# MB_RELAY.net
KiCad netlist of a schematic drawn in Altium Designer
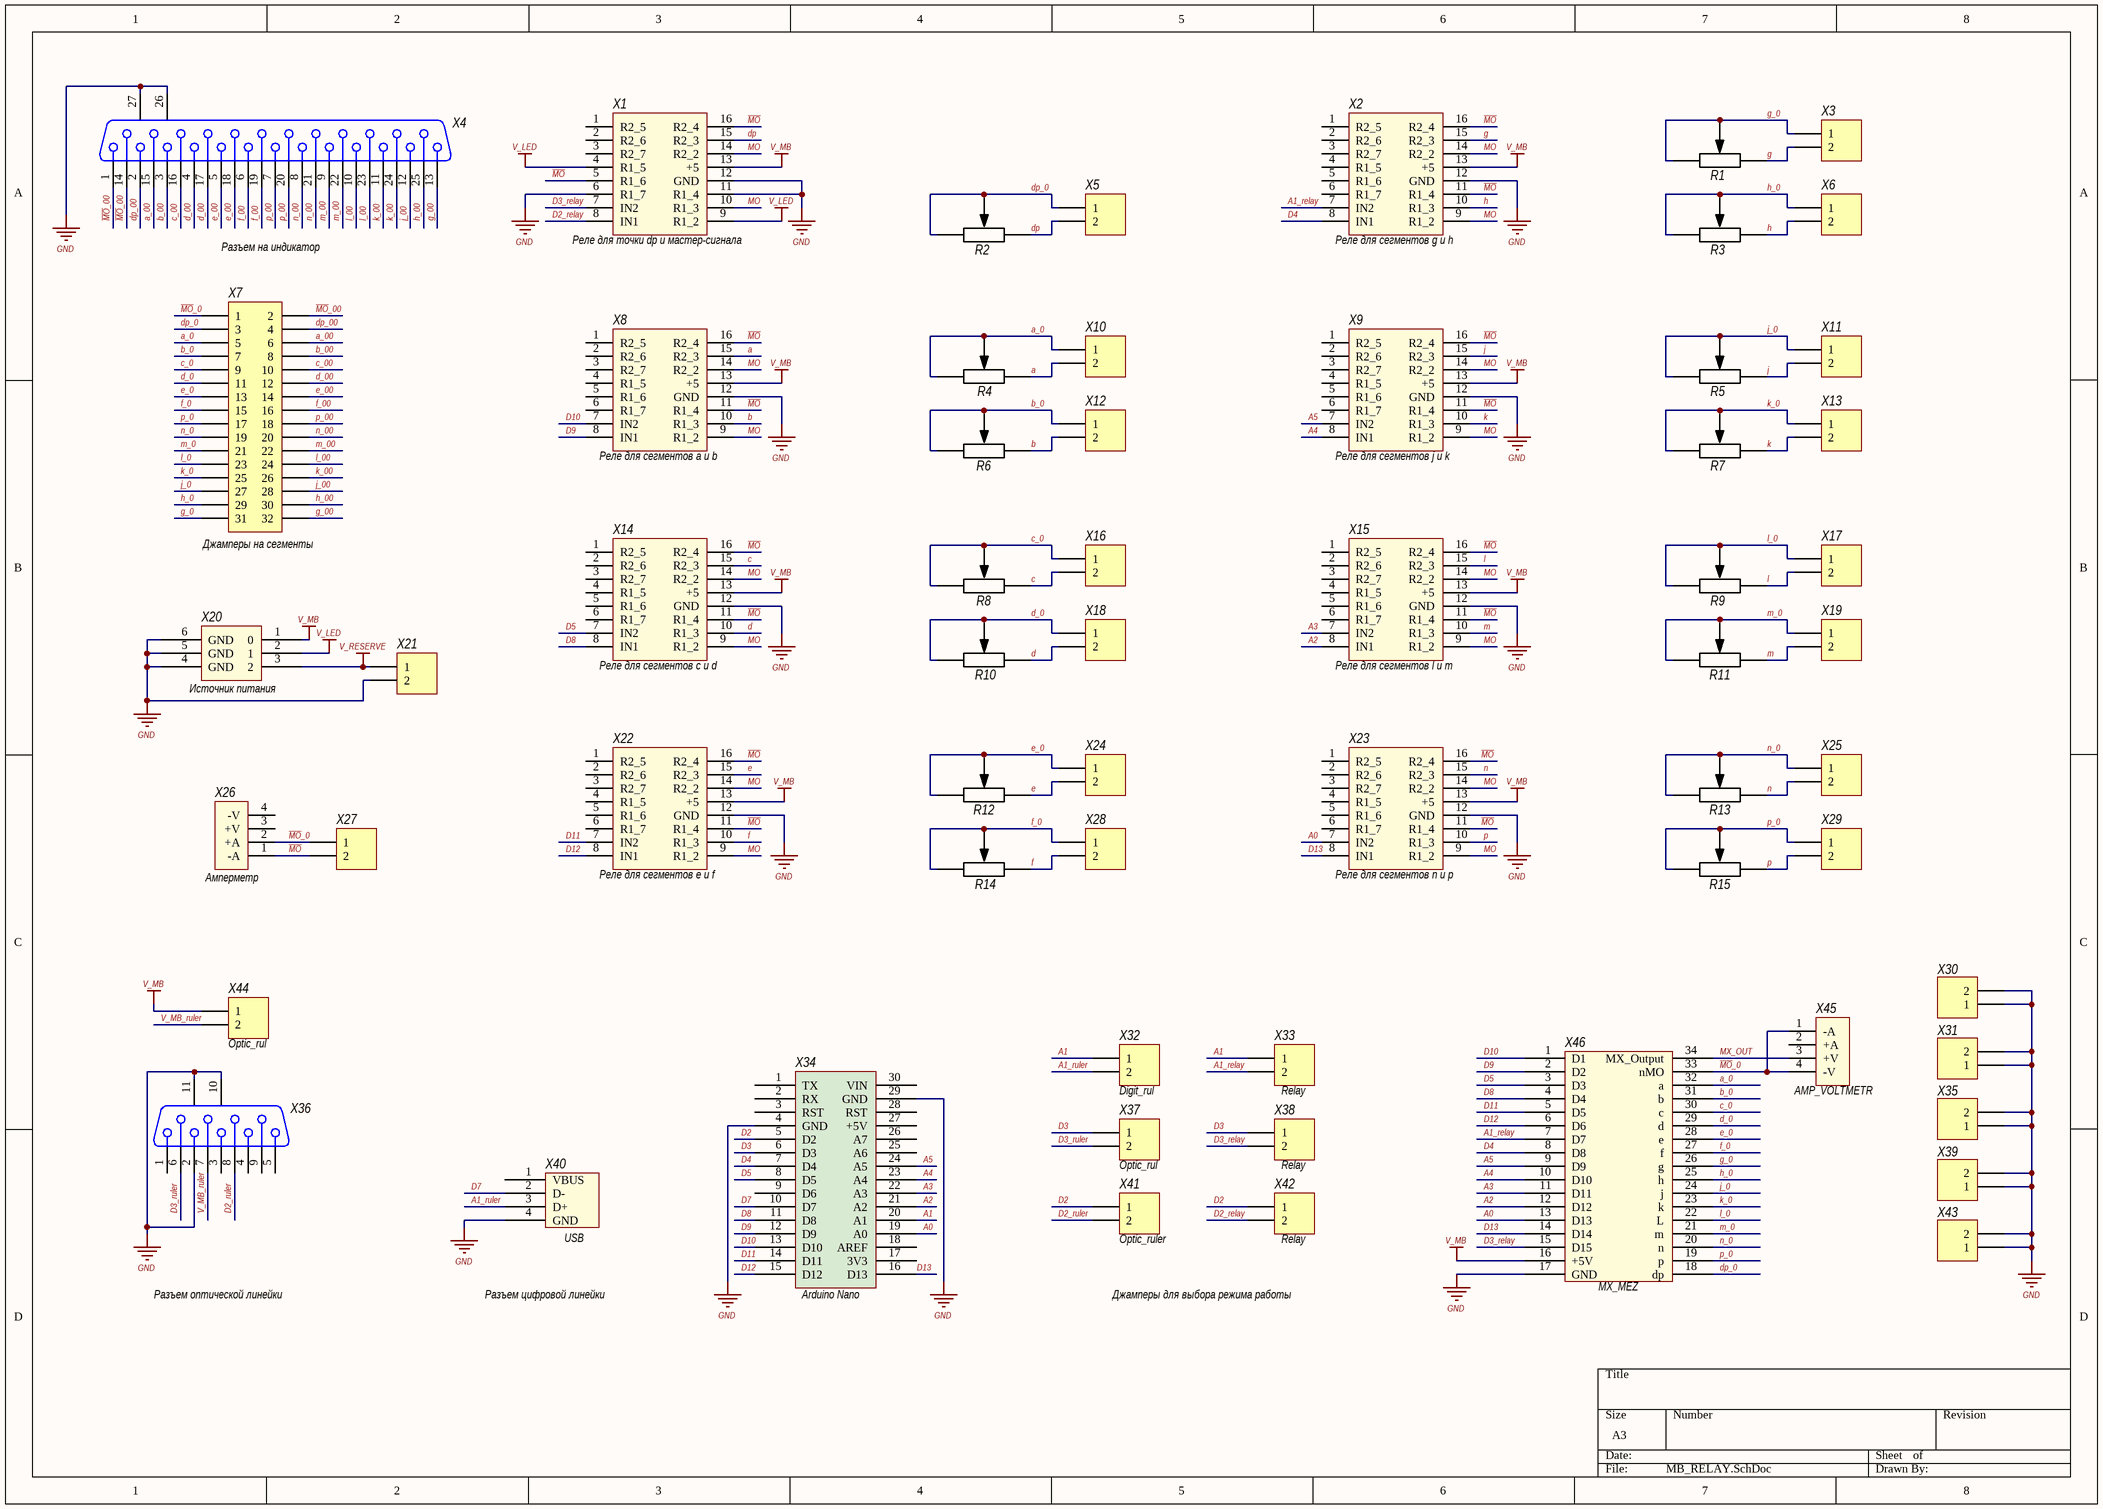
[diagram p0: MB_RELAY.SchDoc]

(export (version "E")
  (design (tool "Eeschema 10.0.6"))
  (components
    (comp (ref "R1")
      (value "RES 3266W")
      (footprint "aab_Passive:RES 3266W")
      (libsource (lib "aab_Schlib") (part "RES 3266W"))
    )
    (comp (ref "R2")
      (value "RES 3266W")
      (footprint "aab_Passive:RES 3266W")
      (libsource (lib "aab_Schlib") (part "RES 3266W"))
    )
    (comp (ref "R3")
      (value "RES 3266W")
      (footprint "aab_Passive:RES 3266W")
      (libsource (lib "aab_Schlib") (part "RES 3266W"))
    )
    (comp (ref "R4")
      (value "Переменнный резистор для")
      (footprint "aab_Passive:RES 3266W")
      (libsource (lib "aab_Schlib") (part "RES 3266W"))
    )
    (comp (ref "R5")
      (value "RES 3266W")
      (footprint "aab_Passive:RES 3266W")
      (libsource (lib "aab_Schlib") (part "RES 3266W"))
    )
    (comp (ref "R6")
      (value "RES 3266W")
      (footprint "aab_Passive:RES 3266W")
      (libsource (lib "aab_Schlib") (part "RES 3266W"))
    )
    (comp (ref "R7")
      (value "RES 3266W")
      (footprint "aab_Passive:RES 3266W")
      (libsource (lib "aab_Schlib") (part "RES 3266W"))
    )
    (comp (ref "R8")
      (value "RES 3266W")
      (footprint "aab_Passive:RES 3266W")
      (libsource (lib "aab_Schlib") (part "RES 3266W"))
    )
    (comp (ref "R9")
      (value "RES 3266W")
      (footprint "aab_Passive:RES 3266W")
      (libsource (lib "aab_Schlib") (part "RES 3266W"))
    )
    (comp (ref "R10")
      (value "RES 3266W")
      (footprint "aab_Passive:RES 3266W")
      (libsource (lib "aab_Schlib") (part "RES 3266W"))
    )
    (comp (ref "R11")
      (value "RES 3266W")
      (footprint "aab_Passive:RES 3266W")
      (libsource (lib "aab_Schlib") (part "RES 3266W"))
    )
    (comp (ref "R12")
      (value "RES 3266W")
      (footprint "aab_Passive:RES 3266W")
      (libsource (lib "aab_Schlib") (part "RES 3266W"))
    )
    (comp (ref "R13")
      (value "RES 3266W")
      (footprint "aab_Passive:RES 3266W")
      (libsource (lib "aab_Schlib") (part "RES 3266W"))
    )
    (comp (ref "R14")
      (value "RES 3266W")
      (footprint "aab_Passive:RES 3266W")
      (libsource (lib "aab_Schlib") (part "RES 3266W"))
    )
    (comp (ref "R15")
      (value "RES 3266W")
      (footprint "aab_Passive:RES 3266W")
      (libsource (lib "aab_Schlib") (part "RES 3266W"))
    )
    (comp (ref "X1")
      (value "Реле для точки dp и мастер-сигнала")
      (footprint "MEZ_RELAY")
      (libsource (lib "msp_SchLib") (part "MEZ_RELAY"))
    )
    (comp (ref "X2")
      (value "Реле для сегментов g и h")
      (footprint "MEZ_RELAY")
      (libsource (lib "msp_SchLib") (part "MEZ_RELAY"))
    )
    (comp (ref "X3")
      (value "GND")
      (footprint "HDR1X2")
      (description "Header, 2-Pin")
      (fields (field (name "PUBLISHER") "Altium Limited"))
      (libsource (lib "Miscellaneous Connectors") (part "Header 2"))
    )
    (comp (ref "X4")
      (value "D Connector 25")
      (footprint "DSUB1.385-2H25A")
      (description "Receptacle Assembly, 25 Position, Right Angle")
      (fields (field (name "PUBLISHER") "Altium Limited"))
      (libsource (lib "Miscellaneous Connectors") (part "D Connector 25"))
    )
    (comp (ref "X5")
      (value "GND")
      (footprint "HDR1X2")
      (description "Header, 2-Pin")
      (fields (field (name "PUBLISHER") "Altium Limited"))
      (libsource (lib "Miscellaneous Connectors") (part "Header 2"))
    )
    (comp (ref "X6")
      (value "GND")
      (footprint "HDR1X2")
      (description "Header, 2-Pin")
      (fields (field (name "PUBLISHER") "Altium Limited"))
      (libsource (lib "Miscellaneous Connectors") (part "Header 2"))
    )
    (comp (ref "X7")
      (value "Header 16X2")
      (footprint "HDR2X16")
      (description "Header, 16-Pin, Dual row")
      (fields (field (name "PUBLISHER") "Altium Limited"))
      (libsource (lib "Miscellaneous Connectors") (part "Header 16X2"))
    )
    (comp (ref "X8")
      (value "Реле для сегментов a и b")
      (footprint "MEZ_RELAY")
      (libsource (lib "msp_SchLib") (part "MEZ_RELAY"))
    )
    (comp (ref "X9")
      (value "Реле для сегментов j и k")
      (footprint "MEZ_RELAY")
      (libsource (lib "msp_SchLib") (part "MEZ_RELAY"))
    )
    (comp (ref "X10")
      (value "Header 2")
      (footprint "HDR1X2")
      (description "Header, 2-Pin")
      (fields (field (name "PUBLISHER") "Altium Limited"))
      (libsource (lib "Miscellaneous Connectors") (part "Header 2"))
    )
    (comp (ref "X11")
      (value "Header 2")
      (footprint "HDR1X2")
      (description "Header, 2-Pin")
      (fields (field (name "PUBLISHER") "Altium Limited"))
      (libsource (lib "Miscellaneous Connectors") (part "Header 2"))
    )
    (comp (ref "X12")
      (value "Header 2")
      (footprint "HDR1X2")
      (description "Header, 2-Pin")
      (fields (field (name "PUBLISHER") "Altium Limited"))
      (libsource (lib "Miscellaneous Connectors") (part "Header 2"))
    )
    (comp (ref "X13")
      (value "Header 2")
      (footprint "HDR1X2")
      (description "Header, 2-Pin")
      (fields (field (name "PUBLISHER") "Altium Limited"))
      (libsource (lib "Miscellaneous Connectors") (part "Header 2"))
    )
    (comp (ref "X14")
      (value "Реле для сегментов c и d")
      (footprint "MEZ_RELAY")
      (libsource (lib "msp_SchLib") (part "MEZ_RELAY"))
    )
    (comp (ref "X15")
      (value "Реле для сегментов l и m")
      (footprint "MEZ_RELAY")
      (libsource (lib "msp_SchLib") (part "MEZ_RELAY"))
    )
    (comp (ref "X16")
      (value "Header 2")
      (footprint "HDR1X2")
      (description "Header, 2-Pin")
      (fields (field (name "PUBLISHER") "Altium Limited"))
      (libsource (lib "Miscellaneous Connectors") (part "Header 2"))
    )
    (comp (ref "X17")
      (value "GND")
      (footprint "HDR1X2")
      (description "Header, 2-Pin")
      (fields (field (name "PUBLISHER") "Altium Limited"))
      (libsource (lib "Miscellaneous Connectors") (part "Header 2"))
    )
    (comp (ref "X18")
      (value "Header 2")
      (footprint "HDR1X2")
      (description "Header, 2-Pin")
      (fields (field (name "PUBLISHER") "Altium Limited"))
      (libsource (lib "Miscellaneous Connectors") (part "Header 2"))
    )
    (comp (ref "X19")
      (value "GND")
      (footprint "HDR1X2")
      (description "Header, 2-Pin")
      (fields (field (name "PUBLISHER") "Altium Limited"))
      (libsource (lib "Miscellaneous Connectors") (part "Header 2"))
    )
    (comp (ref "X20")
      (value "Источник питания")
      (footprint "vpl_Passive:POWER")
      (libsource (lib "msp_SchLib") (part "POWER"))
    )
    (comp (ref "X21")
      (value "Header 2")
      (footprint "HDR1X2")
      (description "Header, 2-Pin")
      (fields (field (name "PUBLISHER") "Altium Limited"))
      (libsource (lib "Miscellaneous Connectors") (part "Header 2"))
    )
    (comp (ref "X22")
      (value "Реле для сегментов e и f")
      (footprint "MEZ_RELAY")
      (libsource (lib "msp_SchLib") (part "MEZ_RELAY"))
    )
    (comp (ref "X23")
      (value "Реле для сегментов n и p")
      (footprint "MEZ_RELAY")
      (libsource (lib "msp_SchLib") (part "MEZ_RELAY"))
    )
    (comp (ref "X24")
      (value "GND")
      (footprint "HDR1X2")
      (description "Header, 2-Pin")
      (fields (field (name "PUBLISHER") "Altium Limited"))
      (libsource (lib "Miscellaneous Connectors") (part "Header 2"))
    )
    (comp (ref "X25")
      (value "GND")
      (footprint "HDR1X2")
      (description "Header, 2-Pin")
      (fields (field (name "PUBLISHER") "Altium Limited"))
      (libsource (lib "Miscellaneous Connectors") (part "Header 2"))
    )
    (comp (ref "X26")
      (value "Амперметр")
      (footprint "vpl_Passive:AMP_VOLTMETER")
      (libsource (lib "msp_SchLib") (part "AMP_VOLTMETR"))
    )
    (comp (ref "X27")
      (value "Header 2")
      (footprint "HDR1X2")
      (description "Header, 2-Pin")
      (fields (field (name "PUBLISHER") "Altium Limited"))
      (libsource (lib "Miscellaneous Connectors") (part "Header 2"))
    )
    (comp (ref "X28")
      (value "GND")
      (footprint "HDR1X2")
      (description "Header, 2-Pin")
      (fields (field (name "PUBLISHER") "Altium Limited"))
      (libsource (lib "Miscellaneous Connectors") (part "Header 2"))
    )
    (comp (ref "X29")
      (value "GND")
      (footprint "HDR1X2")
      (description "Header, 2-Pin")
      (fields (field (name "PUBLISHER") "Altium Limited"))
      (libsource (lib "Miscellaneous Connectors") (part "Header 2"))
    )
    (comp (ref "X30")
      (value "Header 2")
      (footprint "HDR1X2")
      (description "Header, 2-Pin")
      (fields (field (name "PUBLISHER") "Altium Limited"))
      (libsource (lib "") (part "Header 2_1"))
    )
    (comp (ref "X31")
      (value "GND")
      (footprint "HDR1X2")
      (description "Header, 2-Pin")
      (fields (field (name "PUBLISHER") "Altium Limited"))
      (libsource (lib "") (part "Header 2_1"))
    )
    (comp (ref "X32")
      (value "Digit_rul")
      (footprint "HDR1X2")
      (description "Header, 2-Pin")
      (fields (field (name "PUBLISHER") "Altium Limited"))
      (libsource (lib "Miscellaneous Connectors") (part "Header 2"))
    )
    (comp (ref "X33")
      (value "Relay")
      (footprint "HDR1X2")
      (description "Header, 2-Pin")
      (fields (field (name "PUBLISHER") "Altium Limited"))
      (libsource (lib "Miscellaneous Connectors") (part "Header 2"))
    )
    (comp (ref "X34")
      (value "Arduino Nano")
      (footprint "PCBComponent_1")
      (libsource (lib "Nano") (part "Component_1"))
    )
    (comp (ref "X35")
      (value "GND")
      (footprint "HDR1X2")
      (description "Header, 2-Pin")
      (fields (field (name "PUBLISHER") "Altium Limited"))
      (libsource (lib "") (part "Header 2_1"))
    )
    (comp (ref "X36")
      (value "D Connector 9")
      (footprint "DSUB1.385-2H9")
      (description "Receptacle Assembly, 9 Position, Right Angle")
      (fields (field (name "PUBLISHER") "Altium Limited"))
      (libsource (lib "Miscellaneous Connectors") (part "D Connector 9"))
    )
    (comp (ref "X37")
      (value "Optic_rul")
      (footprint "HDR1X2")
      (description "Header, 2-Pin")
      (fields (field (name "PUBLISHER") "Altium Limited"))
      (libsource (lib "Miscellaneous Connectors") (part "Header 2"))
    )
    (comp (ref "X38")
      (value "Relay")
      (footprint "HDR1X2")
      (description "Header, 2-Pin")
      (fields (field (name "PUBLISHER") "Altium Limited"))
      (libsource (lib "Miscellaneous Connectors") (part "Header 2"))
    )
    (comp (ref "X39")
      (value "GND")
      (footprint "HDR1X2")
      (description "Header, 2-Pin")
      (fields (field (name "PUBLISHER") "Altium Limited"))
      (libsource (lib "") (part "Header 2_1"))
    )
    (comp (ref "X40") (value "USB") (footprint "USB") (libsource (lib "msp_SchLib") (part "USB")))
    (comp (ref "X41")
      (value "Optic_ruler")
      (footprint "HDR1X2")
      (description "Header, 2-Pin")
      (fields (field (name "PUBLISHER") "Altium Limited"))
      (libsource (lib "Miscellaneous Connectors") (part "Header 2"))
    )
    (comp (ref "X42")
      (value "Relay")
      (footprint "HDR1X2")
      (description "Header, 2-Pin")
      (fields (field (name "PUBLISHER") "Altium Limited"))
      (libsource (lib "Miscellaneous Connectors") (part "Header 2"))
    )
    (comp (ref "X43")
      (value "GND")
      (footprint "HDR1X2")
      (description "Header, 2-Pin")
      (fields (field (name "PUBLISHER") "Altium Limited"))
      (libsource (lib "") (part "Header 2_1"))
    )
    (comp (ref "X44")
      (value "Optic_rul")
      (footprint "HDR1X2")
      (description "Header, 2-Pin")
      (fields (field (name "PUBLISHER") "Altium Limited"))
      (libsource (lib "Miscellaneous Connectors") (part "Header 2"))
    )
    (comp (ref "X45")
      (value "AMP_VOLTMETR")
      (footprint "AMP_VOLTMETR")
      (libsource (lib "") (part "AMP_VOLTMETR_1"))
    )
    (comp (ref "X46") (value "MX_MEZ") (footprint "MX_MEZ") (libsource (lib "msp_SchLib") (part "MX_MEZ")))
  )
  (nets
    (net (code "1") (name "/A0") (class "Default")
      (node (ref "X23") (pin "7") (pinfunction "IN2_7") (pintype "passive"))
      (node (ref "X34") (pin "19") (pinfunction "A0_19") (pintype "passive"))
      (node (ref "X46") (pin "13") (pinfunction "D13_13") (pintype "passive"))
    )
    (net (code "2") (name "/A1") (class "Default")
      (node (ref "X32") (pin "1") (pinfunction "1_1") (pintype "passive"))
      (node (ref "X33") (pin "1") (pinfunction "1_1") (pintype "passive"))
      (node (ref "X34") (pin "20") (pinfunction "A1_20") (pintype "passive"))
    )
    (net (code "3") (name "/A1_relay") (class "Default")
      (node (ref "X2") (pin "7") (pinfunction "IN2_7") (pintype "passive"))
      (node (ref "X33") (pin "2") (pinfunction "2_2") (pintype "passive"))
      (node (ref "X46") (pin "7") (pinfunction "D7_7") (pintype "passive"))
    )
    (net (code "4") (name "/A1_ruler") (class "Default")
      (node (ref "X32") (pin "2") (pinfunction "2_2") (pintype "passive"))
      (node (ref "X40") (pin "3") (pinfunction "D+_3") (pintype "passive"))
    )
    (net (code "5") (name "/A2") (class "Default")
      (node (ref "X15") (pin "8") (pinfunction "IN1_8") (pintype "passive"))
      (node (ref "X34") (pin "21") (pinfunction "A2_21") (pintype "passive"))
      (node (ref "X46") (pin "12") (pinfunction "D12_12") (pintype "passive"))
    )
    (net (code "6") (name "/A3") (class "Default")
      (node (ref "X15") (pin "7") (pinfunction "IN2_7") (pintype "passive"))
      (node (ref "X34") (pin "22") (pinfunction "A3_22") (pintype "passive"))
      (node (ref "X46") (pin "11") (pinfunction "D11_11") (pintype "passive"))
    )
    (net (code "7") (name "/A4") (class "Default")
      (node (ref "X34") (pin "23") (pinfunction "A4_23") (pintype "passive"))
      (node (ref "X46") (pin "10") (pinfunction "D10_10") (pintype "passive"))
      (node (ref "X9") (pin "8") (pinfunction "IN1_8") (pintype "passive"))
    )
    (net (code "8") (name "/A5") (class "Default")
      (node (ref "X34") (pin "24") (pinfunction "A5_24") (pintype "passive"))
      (node (ref "X46") (pin "9") (pinfunction "D9_9") (pintype "passive"))
      (node (ref "X9") (pin "7") (pinfunction "IN2_7") (pintype "passive"))
    )
    (net (code "9") (name "/D2") (class "Default")
      (node (ref "X34") (pin "5") (pinfunction "D2_5") (pintype "passive"))
      (node (ref "X41") (pin "1") (pinfunction "1_1") (pintype "passive"))
      (node (ref "X42") (pin "1") (pinfunction "1_1") (pintype "passive"))
    )
    (net (code "10") (name "/D2_relay") (class "Default")
      (node (ref "X1") (pin "8") (pinfunction "IN1_8") (pintype "passive"))
      (node (ref "X42") (pin "2") (pinfunction "2_2") (pintype "passive"))
    )
    (net (code "11") (name "/D2_ruler") (class "Default")
      (node (ref "X36") (pin "8") (pinfunction "8_8") (pintype "passive"))
      (node (ref "X41") (pin "2") (pinfunction "2_2") (pintype "passive"))
    )
    (net (code "12") (name "/D3") (class "Default")
      (node (ref "X34") (pin "6") (pinfunction "D3_6") (pintype "passive"))
      (node (ref "X37") (pin "1") (pinfunction "1_1") (pintype "passive"))
      (node (ref "X38") (pin "1") (pinfunction "1_1") (pintype "passive"))
    )
    (net (code "13") (name "/D3_relay") (class "Default")
      (node (ref "X1") (pin "7") (pinfunction "IN2_7") (pintype "passive"))
      (node (ref "X38") (pin "2") (pinfunction "2_2") (pintype "passive"))
      (node (ref "X46") (pin "15") (pinfunction "D15_15") (pintype "passive"))
    )
    (net (code "14") (name "/D3_ruler") (class "Default")
      (node (ref "X36") (pin "6") (pinfunction "6_6") (pintype "passive"))
      (node (ref "X37") (pin "2") (pinfunction "2_2") (pintype "passive"))
    )
    (net (code "15") (name "/D4") (class "Default")
      (node (ref "X2") (pin "8") (pinfunction "IN1_8") (pintype "passive"))
      (node (ref "X34") (pin "7") (pinfunction "D4_7") (pintype "passive"))
      (node (ref "X46") (pin "8") (pinfunction "D8_8") (pintype "passive"))
    )
    (net (code "16") (name "/D5") (class "Default")
      (node (ref "X14") (pin "7") (pinfunction "IN2_7") (pintype "passive"))
      (node (ref "X34") (pin "8") (pinfunction "D5_8") (pintype "passive"))
      (node (ref "X46") (pin "3") (pinfunction "D3_3") (pintype "passive"))
    )
    (net (code "17") (name "/D7") (class "Default")
      (node (ref "X34") (pin "10") (pinfunction "D7_10") (pintype "passive"))
      (node (ref "X40") (pin "2") (pinfunction "D-_2") (pintype "passive"))
    )
    (net (code "18") (name "/D8") (class "Default")
      (node (ref "X14") (pin "8") (pinfunction "IN1_8") (pintype "passive"))
      (node (ref "X34") (pin "11") (pinfunction "D8_11") (pintype "passive"))
      (node (ref "X46") (pin "4") (pinfunction "D4_4") (pintype "passive"))
    )
    (net (code "19") (name "/D9") (class "Default")
      (node (ref "X34") (pin "12") (pinfunction "D9_12") (pintype "passive"))
      (node (ref "X46") (pin "2") (pinfunction "D2_2") (pintype "passive"))
      (node (ref "X8") (pin "8") (pinfunction "IN1_8") (pintype "passive"))
    )
    (net (code "20") (name "/D10") (class "Default")
      (node (ref "X34") (pin "13") (pinfunction "D10_13") (pintype "passive"))
      (node (ref "X46") (pin "1") (pinfunction "D1_1") (pintype "passive"))
      (node (ref "X8") (pin "7") (pinfunction "IN2_7") (pintype "passive"))
    )
    (net (code "21") (name "/D11") (class "Default")
      (node (ref "X22") (pin "7") (pinfunction "IN2_7") (pintype "passive"))
      (node (ref "X34") (pin "14") (pinfunction "D11_14") (pintype "passive"))
      (node (ref "X46") (pin "5") (pinfunction "D5_5") (pintype "passive"))
    )
    (net (code "22") (name "/D12") (class "Default")
      (node (ref "X22") (pin "8") (pinfunction "IN1_8") (pintype "passive"))
      (node (ref "X34") (pin "15") (pinfunction "D12_15") (pintype "passive"))
      (node (ref "X46") (pin "6") (pinfunction "D6_6") (pintype "passive"))
    )
    (net (code "23") (name "/D13") (class "Default")
      (node (ref "X23") (pin "8") (pinfunction "IN1_8") (pintype "passive"))
      (node (ref "X34") (pin "16") (pinfunction "D13_16") (pintype "passive"))
      (node (ref "X46") (pin "14") (pinfunction "D14_14") (pintype "passive"))
    )
    (net (code "24") (name "/MO") (class "Default")
      (node (ref "X1") (pin "10") (pinfunction "R1_3_10") (pintype "passive"))
      (node (ref "X1") (pin "14") (pinfunction "R2_2_14") (pintype "passive"))
      (node (ref "X14") (pin "14") (pinfunction "R2_2_14") (pintype "passive"))
      (node (ref "X14") (pin "9") (pinfunction "R1_2_9") (pintype "passive"))
      (node (ref "X15") (pin "14") (pinfunction "R2_2_14") (pintype "passive"))
      (node (ref "X15") (pin "9") (pinfunction "R1_2_9") (pintype "passive"))
      (node (ref "X2") (pin "14") (pinfunction "R2_2_14") (pintype "passive"))
      (node (ref "X2") (pin "9") (pinfunction "R1_2_9") (pintype "passive"))
      (node (ref "X22") (pin "14") (pinfunction "R2_2_14") (pintype "passive"))
      (node (ref "X22") (pin "9") (pinfunction "R1_2_9") (pintype "passive"))
      (node (ref "X23") (pin "14") (pinfunction "R2_2_14") (pintype "passive"))
      (node (ref "X23") (pin "9") (pinfunction "R1_2_9") (pintype "passive"))
      (node (ref "X8") (pin "14") (pinfunction "R2_2_14") (pintype "passive"))
      (node (ref "X8") (pin "9") (pinfunction "R1_2_9") (pintype "passive"))
      (node (ref "X9") (pin "14") (pinfunction "R2_2_14") (pintype "passive"))
      (node (ref "X9") (pin "9") (pinfunction "R1_2_9") (pintype "passive"))
    )
    (net (code "25") (name "/MX_OUT") (class "Default")
      (node (ref "X45") (pin "3") (pinfunction "+V_3") (pintype "passive"))
      (node (ref "X46") (pin "34") (pinfunction "MX_Output_34") (pintype "passive"))
    )
    (net (code "26") (name "/V_MB_ruler") (class "Default")
      (node (ref "X36") (pin "7") (pinfunction "7_7") (pintype "passive"))
      (node (ref "X44") (pin "2") (pinfunction "2_2") (pintype "passive"))
    )
    (net (code "27") (name "/a") (class "Default")
      (node (ref "R4") (pin "3") (pinfunction "3_3") (pintype "passive"))
      (node (ref "X10") (pin "2") (pinfunction "2_2") (pintype "passive"))
      (node (ref "X8") (pin "15") (pinfunction "R2_3_15") (pintype "passive"))
    )
    (net (code "28") (name "/a_0") (class "Default")
      (node (ref "R4") (pin "1") (pinfunction "1_1") (pintype "passive"))
      (node (ref "R4") (pin "2") (pinfunction "2_2") (pintype "passive"))
      (node (ref "X10") (pin "1") (pinfunction "1_1") (pintype "passive"))
      (node (ref "X46") (pin "32") (pinfunction "a_32") (pintype "passive"))
      (node (ref "X7") (pin "5") (pinfunction "5_5") (pintype "passive"))
    )
    (net (code "29") (name "/a_00") (class "Default")
      (node (ref "X4") (pin "15") (pinfunction "15_15") (pintype "passive"))
      (node (ref "X7") (pin "6") (pinfunction "6_6") (pintype "passive"))
    )
    (net (code "30") (name "/b") (class "Default")
      (node (ref "R6") (pin "3") (pinfunction "3_3") (pintype "passive"))
      (node (ref "X12") (pin "2") (pinfunction "2_2") (pintype "passive"))
      (node (ref "X8") (pin "10") (pinfunction "R1_3_10") (pintype "passive"))
    )
    (net (code "31") (name "/b_0") (class "Default")
      (node (ref "R6") (pin "1") (pinfunction "1_1") (pintype "passive"))
      (node (ref "R6") (pin "2") (pinfunction "2_2") (pintype "passive"))
      (node (ref "X12") (pin "1") (pinfunction "1_1") (pintype "passive"))
      (node (ref "X46") (pin "31") (pinfunction "b_31") (pintype "passive"))
      (node (ref "X7") (pin "7") (pinfunction "7_7") (pintype "passive"))
    )
    (net (code "32") (name "/b_00") (class "Default")
      (node (ref "X4") (pin "3") (pinfunction "3_3") (pintype "passive"))
      (node (ref "X7") (pin "8") (pinfunction "8_8") (pintype "passive"))
    )
    (net (code "33") (name "/c") (class "Default")
      (node (ref "R8") (pin "3") (pinfunction "3_3") (pintype "passive"))
      (node (ref "X14") (pin "15") (pinfunction "R2_3_15") (pintype "passive"))
      (node (ref "X16") (pin "2") (pinfunction "2_2") (pintype "passive"))
    )
    (net (code "34") (name "/c_0") (class "Default")
      (node (ref "R8") (pin "1") (pinfunction "1_1") (pintype "passive"))
      (node (ref "R8") (pin "2") (pinfunction "2_2") (pintype "passive"))
      (node (ref "X16") (pin "1") (pinfunction "1_1") (pintype "passive"))
      (node (ref "X46") (pin "30") (pinfunction "c_30") (pintype "passive"))
      (node (ref "X7") (pin "9") (pinfunction "9_9") (pintype "passive"))
    )
    (net (code "35") (name "/c_00") (class "Default")
      (node (ref "X4") (pin "16") (pinfunction "16_16") (pintype "passive"))
      (node (ref "X7") (pin "10") (pinfunction "10_10") (pintype "passive"))
    )
    (net (code "36") (name "/d") (class "Default")
      (node (ref "R10") (pin "3") (pinfunction "3_3") (pintype "passive"))
      (node (ref "X14") (pin "10") (pinfunction "R1_3_10") (pintype "passive"))
      (node (ref "X18") (pin "2") (pinfunction "2_2") (pintype "passive"))
    )
    (net (code "37") (name "/d_0") (class "Default")
      (node (ref "R10") (pin "1") (pinfunction "1_1") (pintype "passive"))
      (node (ref "R10") (pin "2") (pinfunction "2_2") (pintype "passive"))
      (node (ref "X18") (pin "1") (pinfunction "1_1") (pintype "passive"))
      (node (ref "X46") (pin "29") (pinfunction "d_29") (pintype "passive"))
      (node (ref "X7") (pin "11") (pinfunction "11_11") (pintype "passive"))
    )
    (net (code "38") (name "/d_00") (class "Default")
      (node (ref "X4") (pin "17") (pinfunction "17_17") (pintype "passive"))
      (node (ref "X4") (pin "4") (pinfunction "4_4") (pintype "passive"))
      (node (ref "X7") (pin "12") (pinfunction "12_12") (pintype "passive"))
    )
    (net (code "39") (name "/dp") (class "Default")
      (node (ref "R2") (pin "3") (pinfunction "3_3") (pintype "passive"))
      (node (ref "X1") (pin "15") (pinfunction "R2_3_15") (pintype "passive"))
      (node (ref "X5") (pin "2") (pinfunction "2_2") (pintype "passive"))
    )
    (net (code "40") (name "/dp_00") (class "Default")
      (node (ref "X4") (pin "2") (pinfunction "2_2") (pintype "passive"))
      (node (ref "X7") (pin "4") (pinfunction "4_4") (pintype "passive"))
    )
    (net (code "41") (name "/dp_0") (class "Default")
      (node (ref "R2") (pin "1") (pinfunction "1_1") (pintype "passive"))
      (node (ref "R2") (pin "2") (pinfunction "2_2") (pintype "passive"))
      (node (ref "X46") (pin "18") (pinfunction "dp_18") (pintype "passive"))
      (node (ref "X5") (pin "1") (pinfunction "1_1") (pintype "passive"))
      (node (ref "X7") (pin "3") (pinfunction "3_3") (pintype "passive"))
    )
    (net (code "42") (name "/e") (class "Default")
      (node (ref "R12") (pin "3") (pinfunction "3_3") (pintype "passive"))
      (node (ref "X22") (pin "15") (pinfunction "R2_3_15") (pintype "passive"))
      (node (ref "X24") (pin "2") (pinfunction "2_2") (pintype "passive"))
    )
    (net (code "43") (name "/e_0") (class "Default")
      (node (ref "R12") (pin "1") (pinfunction "1_1") (pintype "passive"))
      (node (ref "R12") (pin "2") (pinfunction "2_2") (pintype "passive"))
      (node (ref "X24") (pin "1") (pinfunction "1_1") (pintype "passive"))
      (node (ref "X46") (pin "28") (pinfunction "e_28") (pintype "passive"))
      (node (ref "X7") (pin "13") (pinfunction "13_13") (pintype "passive"))
    )
    (net (code "44") (name "/e_00") (class "Default")
      (node (ref "X4") (pin "18") (pinfunction "18_18") (pintype "passive"))
      (node (ref "X4") (pin "5") (pinfunction "5_5") (pintype "passive"))
      (node (ref "X7") (pin "14") (pinfunction "14_14") (pintype "passive"))
    )
    (net (code "45") (name "/f") (class "Default")
      (node (ref "R14") (pin "3") (pinfunction "3_3") (pintype "passive"))
      (node (ref "X22") (pin "10") (pinfunction "R1_3_10") (pintype "passive"))
      (node (ref "X28") (pin "2") (pinfunction "2_2") (pintype "passive"))
    )
    (net (code "46") (name "/f_00") (class "Default")
      (node (ref "X4") (pin "19") (pinfunction "19_19") (pintype "passive"))
      (node (ref "X4") (pin "6") (pinfunction "6_6") (pintype "passive"))
      (node (ref "X7") (pin "16") (pinfunction "16_16") (pintype "passive"))
    )
    (net (code "47") (name "/f_0") (class "Default")
      (node (ref "R14") (pin "1") (pinfunction "1_1") (pintype "passive"))
      (node (ref "R14") (pin "2") (pinfunction "2_2") (pintype "passive"))
      (node (ref "X28") (pin "1") (pinfunction "1_1") (pintype "passive"))
      (node (ref "X46") (pin "27") (pinfunction "f_27") (pintype "passive"))
      (node (ref "X7") (pin "15") (pinfunction "15_15") (pintype "passive"))
    )
    (net (code "48") (name "/g") (class "Default")
      (node (ref "R1") (pin "3") (pinfunction "3_3") (pintype "passive"))
      (node (ref "X2") (pin "15") (pinfunction "R2_3_15") (pintype "passive"))
      (node (ref "X3") (pin "2") (pinfunction "2_2") (pintype "passive"))
    )
    (net (code "49") (name "/g_0") (class "Default")
      (node (ref "R1") (pin "1") (pinfunction "1_1") (pintype "passive"))
      (node (ref "R1") (pin "2") (pinfunction "2_2") (pintype "passive"))
      (node (ref "X3") (pin "1") (pinfunction "1_1") (pintype "passive"))
      (node (ref "X46") (pin "26") (pinfunction "g_26") (pintype "passive"))
      (node (ref "X7") (pin "31") (pinfunction "31_31") (pintype "passive"))
    )
    (net (code "50") (name "/g_00") (class "Default")
      (node (ref "X4") (pin "13") (pinfunction "13_13") (pintype "passive"))
      (node (ref "X7") (pin "32") (pinfunction "32_32") (pintype "passive"))
    )
    (net (code "51") (name "/h") (class "Default")
      (node (ref "R3") (pin "3") (pinfunction "3_3") (pintype "passive"))
      (node (ref "X2") (pin "10") (pinfunction "R1_3_10") (pintype "passive"))
      (node (ref "X6") (pin "2") (pinfunction "2_2") (pintype "passive"))
    )
    (net (code "52") (name "/h_0") (class "Default")
      (node (ref "R3") (pin "1") (pinfunction "1_1") (pintype "passive"))
      (node (ref "R3") (pin "2") (pinfunction "2_2") (pintype "passive"))
      (node (ref "X46") (pin "25") (pinfunction "h_25") (pintype "passive"))
      (node (ref "X6") (pin "1") (pinfunction "1_1") (pintype "passive"))
      (node (ref "X7") (pin "29") (pinfunction "29_29") (pintype "passive"))
    )
    (net (code "53") (name "/h_00") (class "Default")
      (node (ref "X4") (pin "25") (pinfunction "25_25") (pintype "passive"))
      (node (ref "X7") (pin "30") (pinfunction "30_30") (pintype "passive"))
    )
    (net (code "54") (name "/j") (class "Default")
      (node (ref "R5") (pin "3") (pinfunction "3_3") (pintype "passive"))
      (node (ref "X11") (pin "2") (pinfunction "2_2") (pintype "passive"))
      (node (ref "X9") (pin "15") (pinfunction "R2_3_15") (pintype "passive"))
    )
    (net (code "55") (name "/j_0") (class "Default")
      (node (ref "R5") (pin "1") (pinfunction "1_1") (pintype "passive"))
      (node (ref "R5") (pin "2") (pinfunction "2_2") (pintype "passive"))
      (node (ref "X11") (pin "1") (pinfunction "1_1") (pintype "passive"))
      (node (ref "X46") (pin "24") (pinfunction "j_24") (pintype "passive"))
      (node (ref "X7") (pin "27") (pinfunction "27_27") (pintype "passive"))
    )
    (net (code "56") (name "/j_00") (class "Default")
      (node (ref "X4") (pin "12") (pinfunction "12_12") (pintype "passive"))
      (node (ref "X7") (pin "28") (pinfunction "28_28") (pintype "passive"))
    )
    (net (code "57") (name "/k") (class "Default")
      (node (ref "R7") (pin "3") (pinfunction "3_3") (pintype "passive"))
      (node (ref "X13") (pin "2") (pinfunction "2_2") (pintype "passive"))
      (node (ref "X9") (pin "10") (pinfunction "R1_3_10") (pintype "passive"))
    )
    (net (code "58") (name "/k_0") (class "Default")
      (node (ref "R7") (pin "1") (pinfunction "1_1") (pintype "passive"))
      (node (ref "R7") (pin "2") (pinfunction "2_2") (pintype "passive"))
      (node (ref "X13") (pin "1") (pinfunction "1_1") (pintype "passive"))
      (node (ref "X46") (pin "23") (pinfunction "k_23") (pintype "passive"))
      (node (ref "X7") (pin "25") (pinfunction "25_25") (pintype "passive"))
    )
    (net (code "59") (name "/k_00") (class "Default")
      (node (ref "X4") (pin "11") (pinfunction "11_11") (pintype "passive"))
      (node (ref "X4") (pin "24") (pinfunction "24_24") (pintype "passive"))
      (node (ref "X7") (pin "26") (pinfunction "26_26") (pintype "passive"))
    )
    (net (code "60") (name "/l") (class "Default")
      (node (ref "R9") (pin "3") (pinfunction "3_3") (pintype "passive"))
      (node (ref "X15") (pin "15") (pinfunction "R2_3_15") (pintype "passive"))
      (node (ref "X17") (pin "2") (pinfunction "2_2") (pintype "passive"))
    )
    (net (code "61") (name "/l_0") (class "Default")
      (node (ref "R9") (pin "1") (pinfunction "1_1") (pintype "passive"))
      (node (ref "R9") (pin "2") (pinfunction "2_2") (pintype "passive"))
      (node (ref "X17") (pin "1") (pinfunction "1_1") (pintype "passive"))
      (node (ref "X46") (pin "22") (pinfunction "L_22") (pintype "passive"))
      (node (ref "X7") (pin "23") (pinfunction "23_23") (pintype "passive"))
    )
    (net (code "62") (name "/l_00") (class "Default")
      (node (ref "X4") (pin "10") (pinfunction "10_10") (pintype "passive"))
      (node (ref "X4") (pin "23") (pinfunction "23_23") (pintype "passive"))
      (node (ref "X7") (pin "24") (pinfunction "24_24") (pintype "passive"))
    )
    (net (code "63") (name "/m") (class "Default")
      (node (ref "R11") (pin "3") (pinfunction "3_3") (pintype "passive"))
      (node (ref "X15") (pin "10") (pinfunction "R1_3_10") (pintype "passive"))
      (node (ref "X19") (pin "2") (pinfunction "2_2") (pintype "passive"))
    )
    (net (code "64") (name "/m_0") (class "Default")
      (node (ref "R11") (pin "1") (pinfunction "1_1") (pintype "passive"))
      (node (ref "R11") (pin "2") (pinfunction "2_2") (pintype "passive"))
      (node (ref "X19") (pin "1") (pinfunction "1_1") (pintype "passive"))
      (node (ref "X46") (pin "21") (pinfunction "m_21") (pintype "passive"))
      (node (ref "X7") (pin "21") (pinfunction "21_21") (pintype "passive"))
    )
    (net (code "65") (name "/m_00") (class "Default")
      (node (ref "X4") (pin "22") (pinfunction "22_22") (pintype "passive"))
      (node (ref "X4") (pin "9") (pinfunction "9_9") (pintype "passive"))
      (node (ref "X7") (pin "22") (pinfunction "22_22") (pintype "passive"))
    )
    (net (code "66") (name "/n") (class "Default")
      (node (ref "R13") (pin "3") (pinfunction "3_3") (pintype "passive"))
      (node (ref "X23") (pin "15") (pinfunction "R2_3_15") (pintype "passive"))
      (node (ref "X25") (pin "2") (pinfunction "2_2") (pintype "passive"))
    )
    (net (code "67") (name "/n_00") (class "Default")
      (node (ref "X4") (pin "21") (pinfunction "21_21") (pintype "passive"))
      (node (ref "X4") (pin "8") (pinfunction "8_8") (pintype "passive"))
      (node (ref "X7") (pin "20") (pinfunction "20_20") (pintype "passive"))
    )
    (net (code "68") (name "/n_0") (class "Default")
      (node (ref "R13") (pin "1") (pinfunction "1_1") (pintype "passive"))
      (node (ref "R13") (pin "2") (pinfunction "2_2") (pintype "passive"))
      (node (ref "X25") (pin "1") (pinfunction "1_1") (pintype "passive"))
      (node (ref "X46") (pin "20") (pinfunction "n_20") (pintype "passive"))
      (node (ref "X7") (pin "19") (pinfunction "19_19") (pintype "passive"))
    )
    (net (code "69") (name "/p") (class "Default")
      (node (ref "R15") (pin "3") (pinfunction "3_3") (pintype "passive"))
      (node (ref "X23") (pin "10") (pinfunction "R1_3_10") (pintype "passive"))
      (node (ref "X29") (pin "2") (pinfunction "2_2") (pintype "passive"))
    )
    (net (code "70") (name "/p_0") (class "Default")
      (node (ref "R15") (pin "1") (pinfunction "1_1") (pintype "passive"))
      (node (ref "R15") (pin "2") (pinfunction "2_2") (pintype "passive"))
      (node (ref "X29") (pin "1") (pinfunction "1_1") (pintype "passive"))
      (node (ref "X46") (pin "19") (pinfunction "p_19") (pintype "passive"))
      (node (ref "X7") (pin "17") (pinfunction "17_17") (pintype "passive"))
    )
    (net (code "71") (name "/p_00") (class "Default")
      (node (ref "X4") (pin "20") (pinfunction "20_20") (pintype "passive"))
      (node (ref "X4") (pin "7") (pinfunction "7_7") (pintype "passive"))
      (node (ref "X7") (pin "18") (pinfunction "18_18") (pintype "passive"))
    )
    (net (code "72") (name "/~{MO}") (class "Default")
      (node (ref "X1") (pin "16") (pinfunction "R2_4_16") (pintype "passive"))
      (node (ref "X1") (pin "5") (pinfunction "R1_6_5") (pintype "passive"))
      (node (ref "X14") (pin "11") (pinfunction "R1_4_11") (pintype "passive"))
      (node (ref "X14") (pin "16") (pinfunction "R2_4_16") (pintype "passive"))
      (node (ref "X15") (pin "11") (pinfunction "R1_4_11") (pintype "passive"))
      (node (ref "X15") (pin "16") (pinfunction "R2_4_16") (pintype "passive"))
      (node (ref "X2") (pin "11") (pinfunction "R1_4_11") (pintype "passive"))
      (node (ref "X2") (pin "16") (pinfunction "R2_4_16") (pintype "passive"))
      (node (ref "X22") (pin "11") (pinfunction "R1_4_11") (pintype "passive"))
      (node (ref "X22") (pin "16") (pinfunction "R2_4_16") (pintype "passive"))
      (node (ref "X23") (pin "11") (pinfunction "R1_4_11") (pintype "passive"))
      (node (ref "X23") (pin "16") (pinfunction "R2_4_16") (pintype "passive"))
      (node (ref "X26") (pin "1") (pinfunction "-A_1") (pintype "passive"))
      (node (ref "X27") (pin "2") (pinfunction "2_2") (pintype "passive"))
      (node (ref "X8") (pin "11") (pinfunction "R1_4_11") (pintype "passive"))
      (node (ref "X8") (pin "16") (pinfunction "R2_4_16") (pintype "passive"))
      (node (ref "X9") (pin "11") (pinfunction "R1_4_11") (pintype "passive"))
      (node (ref "X9") (pin "16") (pinfunction "R2_4_16") (pintype "passive"))
    )
    (net (code "73") (name "/~{MO}_0") (class "Default")
      (node (ref "X26") (pin "2") (pinfunction "+A_2") (pintype "passive"))
      (node (ref "X27") (pin "1") (pinfunction "1_1") (pintype "passive"))
      (node (ref "X45") (pin "1") (pinfunction "-A_1") (pintype "passive"))
      (node (ref "X45") (pin "4") (pinfunction "-V_4") (pintype "passive"))
      (node (ref "X46") (pin "33") (pinfunction "nMO_33") (pintype "passive"))
      (node (ref "X7") (pin "1") (pinfunction "1_1") (pintype "passive"))
    )
    (net (code "74") (name "/~{MO}_00") (class "Default")
      (node (ref "X4") (pin "1") (pinfunction "1_1") (pintype "passive"))
      (node (ref "X4") (pin "14") (pinfunction "14_14") (pintype "passive"))
      (node (ref "X7") (pin "2") (pinfunction "2_2") (pintype "passive"))
    )
    (net (code "75") (name "GND") (class "Default")
      (node (ref "X1") (pin "11") (pinfunction "R1_4_11") (pintype "passive"))
      (node (ref "X1") (pin "12") (pinfunction "GND_12") (pintype "passive"))
      (node (ref "X1") (pin "6") (pinfunction "R1_7_6") (pintype "passive"))
      (node (ref "X14") (pin "12") (pinfunction "GND_12") (pintype "passive"))
      (node (ref "X15") (pin "12") (pinfunction "GND_12") (pintype "passive"))
      (node (ref "X2") (pin "12") (pinfunction "GND_12") (pintype "passive"))
      (node (ref "X20") (pin "4") (pinfunction "GND_4") (pintype "passive"))
      (node (ref "X20") (pin "5") (pinfunction "GND_5") (pintype "passive"))
      (node (ref "X20") (pin "6") (pinfunction "GND_6") (pintype "passive"))
      (node (ref "X21") (pin "2") (pinfunction "2_2") (pintype "passive"))
      (node (ref "X22") (pin "12") (pinfunction "GND_12") (pintype "passive"))
      (node (ref "X23") (pin "12") (pinfunction "GND_12") (pintype "passive"))
      (node (ref "X30") (pin "1") (pinfunction "1_1") (pintype "passive"))
      (node (ref "X30") (pin "2") (pinfunction "2_2") (pintype "passive"))
      (node (ref "X31") (pin "1") (pinfunction "1_1") (pintype "passive"))
      (node (ref "X31") (pin "2") (pinfunction "2_2") (pintype "passive"))
      (node (ref "X34") (pin "29") (pinfunction "GND_29") (pintype "passive"))
      (node (ref "X34") (pin "4") (pinfunction "GND_4") (pintype "passive"))
      (node (ref "X35") (pin "1") (pinfunction "1_1") (pintype "passive"))
      (node (ref "X35") (pin "2") (pinfunction "2_2") (pintype "passive"))
      (node (ref "X36") (pin "10") (pinfunction "MH1_10") (pintype "passive"))
      (node (ref "X36") (pin "11") (pinfunction "MH2_11") (pintype "passive"))
      (node (ref "X36") (pin "2") (pinfunction "2_2") (pintype "passive"))
      (node (ref "X39") (pin "1") (pinfunction "1_1") (pintype "passive"))
      (node (ref "X39") (pin "2") (pinfunction "2_2") (pintype "passive"))
      (node (ref "X4") (pin "26") (pinfunction "MH1_26") (pintype "passive"))
      (node (ref "X4") (pin "27") (pinfunction "MH2_27") (pintype "passive"))
      (node (ref "X40") (pin "4") (pinfunction "GND_4") (pintype "passive"))
      (node (ref "X43") (pin "1") (pinfunction "1_1") (pintype "passive"))
      (node (ref "X43") (pin "2") (pinfunction "2_2") (pintype "passive"))
      (node (ref "X46") (pin "17") (pinfunction "GND_17") (pintype "passive"))
      (node (ref "X8") (pin "12") (pinfunction "GND_12") (pintype "passive"))
      (node (ref "X9") (pin "12") (pinfunction "GND_12") (pintype "passive"))
    )
    (net (code "76") (name "V_LED") (class "Default")
      (node (ref "X1") (pin "4") (pinfunction "R1_5_4") (pintype "passive"))
      (node (ref "X1") (pin "9") (pinfunction "R1_2_9") (pintype "passive"))
      (node (ref "X20") (pin "2") (pinfunction "1_2") (pintype "passive"))
    )
    (net (code "77") (name "V_MB") (class "Default")
      (node (ref "X1") (pin "13") (pinfunction "+5_13") (pintype "passive"))
      (node (ref "X14") (pin "13") (pinfunction "+5_13") (pintype "passive"))
      (node (ref "X15") (pin "13") (pinfunction "+5_13") (pintype "passive"))
      (node (ref "X2") (pin "13") (pinfunction "+5_13") (pintype "passive"))
      (node (ref "X20") (pin "1") (pinfunction "0_1") (pintype "passive"))
      (node (ref "X22") (pin "13") (pinfunction "+5_13") (pintype "passive"))
      (node (ref "X23") (pin "13") (pinfunction "+5_13") (pintype "passive"))
      (node (ref "X44") (pin "1") (pinfunction "1_1") (pintype "passive"))
      (node (ref "X46") (pin "16") (pinfunction "+5V_16") (pintype "passive"))
      (node (ref "X8") (pin "13") (pinfunction "+5_13") (pintype "passive"))
      (node (ref "X9") (pin "13") (pinfunction "+5_13") (pintype "passive"))
    )
    (net (code "78") (name "V_RESERVE") (class "Default")
      (node (ref "X20") (pin "3") (pinfunction "2_3") (pintype "passive"))
      (node (ref "X21") (pin "1") (pinfunction "1_1") (pintype "passive"))
    )
    (net (code "79") (name "unconnected-(X1-R2_5-Pad1)") (class "Default")
      (node (ref "X1") (pin "1") (pinfunction "R2_5_1") (pintype "passive"))
    )
    (net (code "80") (name "unconnected-(X1-R2_6-Pad2)") (class "Default")
      (node (ref "X1") (pin "2") (pinfunction "R2_6_2") (pintype "passive"))
    )
    (net (code "81") (name "unconnected-(X1-R2_7-Pad3)") (class "Default")
      (node (ref "X1") (pin "3") (pinfunction "R2_7_3") (pintype "passive"))
    )
    (net (code "82") (name "unconnected-(X2-R1_5-Pad4)") (class "Default")
      (node (ref "X2") (pin "4") (pinfunction "R1_5_4") (pintype "passive"))
    )
    (net (code "83") (name "unconnected-(X2-R1_6-Pad5)") (class "Default")
      (node (ref "X2") (pin "5") (pinfunction "R1_6_5") (pintype "passive"))
    )
    (net (code "84") (name "unconnected-(X2-R1_7-Pad6)") (class "Default")
      (node (ref "X2") (pin "6") (pinfunction "R1_7_6") (pintype "passive"))
    )
    (net (code "85") (name "unconnected-(X2-R2_5-Pad1)") (class "Default")
      (node (ref "X2") (pin "1") (pinfunction "R2_5_1") (pintype "passive"))
    )
    (net (code "86") (name "unconnected-(X2-R2_6-Pad2)") (class "Default")
      (node (ref "X2") (pin "2") (pinfunction "R2_6_2") (pintype "passive"))
    )
    (net (code "87") (name "unconnected-(X2-R2_7-Pad3)") (class "Default")
      (node (ref "X2") (pin "3") (pinfunction "R2_7_3") (pintype "passive"))
    )
    (net (code "88") (name "unconnected-(X8-R1_5-Pad4)") (class "Default")
      (node (ref "X8") (pin "4") (pinfunction "R1_5_4") (pintype "passive"))
    )
    (net (code "89") (name "unconnected-(X8-R1_6-Pad5)") (class "Default")
      (node (ref "X8") (pin "5") (pinfunction "R1_6_5") (pintype "passive"))
    )
    (net (code "90") (name "unconnected-(X8-R1_7-Pad6)") (class "Default")
      (node (ref "X8") (pin "6") (pinfunction "R1_7_6") (pintype "passive"))
    )
    (net (code "91") (name "unconnected-(X8-R2_5-Pad1)") (class "Default")
      (node (ref "X8") (pin "1") (pinfunction "R2_5_1") (pintype "passive"))
    )
    (net (code "92") (name "unconnected-(X8-R2_6-Pad2)") (class "Default")
      (node (ref "X8") (pin "2") (pinfunction "R2_6_2") (pintype "passive"))
    )
    (net (code "93") (name "unconnected-(X8-R2_7-Pad3)") (class "Default")
      (node (ref "X8") (pin "3") (pinfunction "R2_7_3") (pintype "passive"))
    )
    (net (code "94") (name "unconnected-(X9-R1_5-Pad4)") (class "Default")
      (node (ref "X9") (pin "4") (pinfunction "R1_5_4") (pintype "passive"))
    )
    (net (code "95") (name "unconnected-(X9-R1_6-Pad5)") (class "Default")
      (node (ref "X9") (pin "5") (pinfunction "R1_6_5") (pintype "passive"))
    )
    (net (code "96") (name "unconnected-(X9-R1_7-Pad6)") (class "Default")
      (node (ref "X9") (pin "6") (pinfunction "R1_7_6") (pintype "passive"))
    )
    (net (code "97") (name "unconnected-(X9-R2_5-Pad1)") (class "Default")
      (node (ref "X9") (pin "1") (pinfunction "R2_5_1") (pintype "passive"))
    )
    (net (code "98") (name "unconnected-(X9-R2_6-Pad2)") (class "Default")
      (node (ref "X9") (pin "2") (pinfunction "R2_6_2") (pintype "passive"))
    )
    (net (code "99") (name "unconnected-(X9-R2_7-Pad3)") (class "Default")
      (node (ref "X9") (pin "3") (pinfunction "R2_7_3") (pintype "passive"))
    )
    (net (code "100") (name "unconnected-(X14-R1_5-Pad4)") (class "Default")
      (node (ref "X14") (pin "4") (pinfunction "R1_5_4") (pintype "passive"))
    )
    (net (code "101") (name "unconnected-(X14-R1_6-Pad5)") (class "Default")
      (node (ref "X14") (pin "5") (pinfunction "R1_6_5") (pintype "passive"))
    )
    (net (code "102") (name "unconnected-(X14-R1_7-Pad6)") (class "Default")
      (node (ref "X14") (pin "6") (pinfunction "R1_7_6") (pintype "passive"))
    )
    (net (code "103") (name "unconnected-(X14-R2_5-Pad1)") (class "Default")
      (node (ref "X14") (pin "1") (pinfunction "R2_5_1") (pintype "passive"))
    )
    (net (code "104") (name "unconnected-(X14-R2_6-Pad2)") (class "Default")
      (node (ref "X14") (pin "2") (pinfunction "R2_6_2") (pintype "passive"))
    )
    (net (code "105") (name "unconnected-(X14-R2_7-Pad3)") (class "Default")
      (node (ref "X14") (pin "3") (pinfunction "R2_7_3") (pintype "passive"))
    )
    (net (code "106") (name "unconnected-(X15-R1_5-Pad4)") (class "Default")
      (node (ref "X15") (pin "4") (pinfunction "R1_5_4") (pintype "passive"))
    )
    (net (code "107") (name "unconnected-(X15-R1_6-Pad5)") (class "Default")
      (node (ref "X15") (pin "5") (pinfunction "R1_6_5") (pintype "passive"))
    )
    (net (code "108") (name "unconnected-(X15-R1_7-Pad6)") (class "Default")
      (node (ref "X15") (pin "6") (pinfunction "R1_7_6") (pintype "passive"))
    )
    (net (code "109") (name "unconnected-(X15-R2_5-Pad1)") (class "Default")
      (node (ref "X15") (pin "1") (pinfunction "R2_5_1") (pintype "passive"))
    )
    (net (code "110") (name "unconnected-(X15-R2_6-Pad2)") (class "Default")
      (node (ref "X15") (pin "2") (pinfunction "R2_6_2") (pintype "passive"))
    )
    (net (code "111") (name "unconnected-(X15-R2_7-Pad3)") (class "Default")
      (node (ref "X15") (pin "3") (pinfunction "R2_7_3") (pintype "passive"))
    )
    (net (code "112") (name "unconnected-(X22-R1_5-Pad4)") (class "Default")
      (node (ref "X22") (pin "4") (pinfunction "R1_5_4") (pintype "passive"))
    )
    (net (code "113") (name "unconnected-(X22-R1_6-Pad5)") (class "Default")
      (node (ref "X22") (pin "5") (pinfunction "R1_6_5") (pintype "passive"))
    )
    (net (code "114") (name "unconnected-(X22-R1_7-Pad6)") (class "Default")
      (node (ref "X22") (pin "6") (pinfunction "R1_7_6") (pintype "passive"))
    )
    (net (code "115") (name "unconnected-(X22-R2_5-Pad1)") (class "Default")
      (node (ref "X22") (pin "1") (pinfunction "R2_5_1") (pintype "passive"))
    )
    (net (code "116") (name "unconnected-(X22-R2_6-Pad2)") (class "Default")
      (node (ref "X22") (pin "2") (pinfunction "R2_6_2") (pintype "passive"))
    )
    (net (code "117") (name "unconnected-(X22-R2_7-Pad3)") (class "Default")
      (node (ref "X22") (pin "3") (pinfunction "R2_7_3") (pintype "passive"))
    )
    (net (code "118") (name "unconnected-(X23-R1_5-Pad4)") (class "Default")
      (node (ref "X23") (pin "4") (pinfunction "R1_5_4") (pintype "passive"))
    )
    (net (code "119") (name "unconnected-(X23-R1_6-Pad5)") (class "Default")
      (node (ref "X23") (pin "5") (pinfunction "R1_6_5") (pintype "passive"))
    )
    (net (code "120") (name "unconnected-(X23-R1_7-Pad6)") (class "Default")
      (node (ref "X23") (pin "6") (pinfunction "R1_7_6") (pintype "passive"))
    )
    (net (code "121") (name "unconnected-(X23-R2_5-Pad1)") (class "Default")
      (node (ref "X23") (pin "1") (pinfunction "R2_5_1") (pintype "passive"))
    )
    (net (code "122") (name "unconnected-(X23-R2_6-Pad2)") (class "Default")
      (node (ref "X23") (pin "2") (pinfunction "R2_6_2") (pintype "passive"))
    )
    (net (code "123") (name "unconnected-(X23-R2_7-Pad3)") (class "Default")
      (node (ref "X23") (pin "3") (pinfunction "R2_7_3") (pintype "passive"))
    )
    (net (code "124") (name "unconnected-(X26-+V-Pad3)") (class "Default")
      (node (ref "X26") (pin "3") (pinfunction "+V_3") (pintype "passive"))
    )
    (net (code "125") (name "unconnected-(X26--V-Pad4)") (class "Default")
      (node (ref "X26") (pin "4") (pinfunction "-V_4") (pintype "passive"))
    )
    (net (code "126") (name "unconnected-(X34-+5V-Pad27)") (class "Default")
      (node (ref "X34") (pin "27") (pinfunction "+5V_27") (pintype "passive"))
    )
    (net (code "127") (name "unconnected-(X34-3V3-Pad17)") (class "Default")
      (node (ref "X34") (pin "17") (pinfunction "3V3_17") (pintype "passive"))
    )
    (net (code "128") (name "unconnected-(X34-A6-Pad25)") (class "Default")
      (node (ref "X34") (pin "25") (pinfunction "A6_25") (pintype "passive"))
    )
    (net (code "129") (name "unconnected-(X34-A7-Pad26)") (class "Default")
      (node (ref "X34") (pin "26") (pinfunction "A7_26") (pintype "passive"))
    )
    (net (code "130") (name "unconnected-(X34-AREF-Pad18)") (class "Default")
      (node (ref "X34") (pin "18") (pinfunction "AREF_18") (pintype "passive"))
    )
    (net (code "131") (name "unconnected-(X34-D6-Pad9)") (class "Default")
      (node (ref "X34") (pin "9") (pinfunction "D6_9") (pintype "passive"))
    )
    (net (code "132") (name "unconnected-(X34-RST-Pad3)") (class "Default")
      (node (ref "X34") (pin "3") (pinfunction "RST_3") (pintype "passive"))
    )
    (net (code "133") (name "unconnected-(X34-RST-Pad28)") (class "Default")
      (node (ref "X34") (pin "28") (pinfunction "RST_28") (pintype "passive"))
    )
    (net (code "134") (name "unconnected-(X34-RX-Pad2)") (class "Default")
      (node (ref "X34") (pin "2") (pinfunction "RX_2") (pintype "passive"))
    )
    (net (code "135") (name "unconnected-(X34-TX-Pad1)") (class "Default")
      (node (ref "X34") (pin "1") (pinfunction "TX_1") (pintype "passive"))
    )
    (net (code "136") (name "unconnected-(X34-VIN-Pad30)") (class "Default")
      (node (ref "X34") (pin "30") (pinfunction "VIN_30") (pintype "passive"))
    )
    (net (code "137") (name "unconnected-(X36-Pad1)") (class "Default")
      (node (ref "X36") (pin "1") (pinfunction "1_1") (pintype "passive"))
    )
    (net (code "138") (name "unconnected-(X36-Pad3)") (class "Default")
      (node (ref "X36") (pin "3") (pinfunction "3_3") (pintype "passive"))
    )
    (net (code "139") (name "unconnected-(X36-Pad4)") (class "Default")
      (node (ref "X36") (pin "4") (pinfunction "4_4") (pintype "passive"))
    )
    (net (code "140") (name "unconnected-(X36-Pad5)") (class "Default")
      (node (ref "X36") (pin "5") (pinfunction "5_5") (pintype "passive"))
    )
    (net (code "141") (name "unconnected-(X36-Pad9)") (class "Default")
      (node (ref "X36") (pin "9") (pinfunction "9_9") (pintype "passive"))
    )
    (net (code "142") (name "unconnected-(X40-VBUS-Pad1)") (class "Default")
      (node (ref "X40") (pin "1") (pinfunction "VBUS_1") (pintype "passive"))
    )
    (net (code "143") (name "unconnected-(X45-+A-Pad2)") (class "Default")
      (node (ref "X45") (pin "2") (pinfunction "+A_2") (pintype "passive"))
    )
  )
)
